# MotherBoard.net
KiCad netlist of a schematic drawn in EAGLE
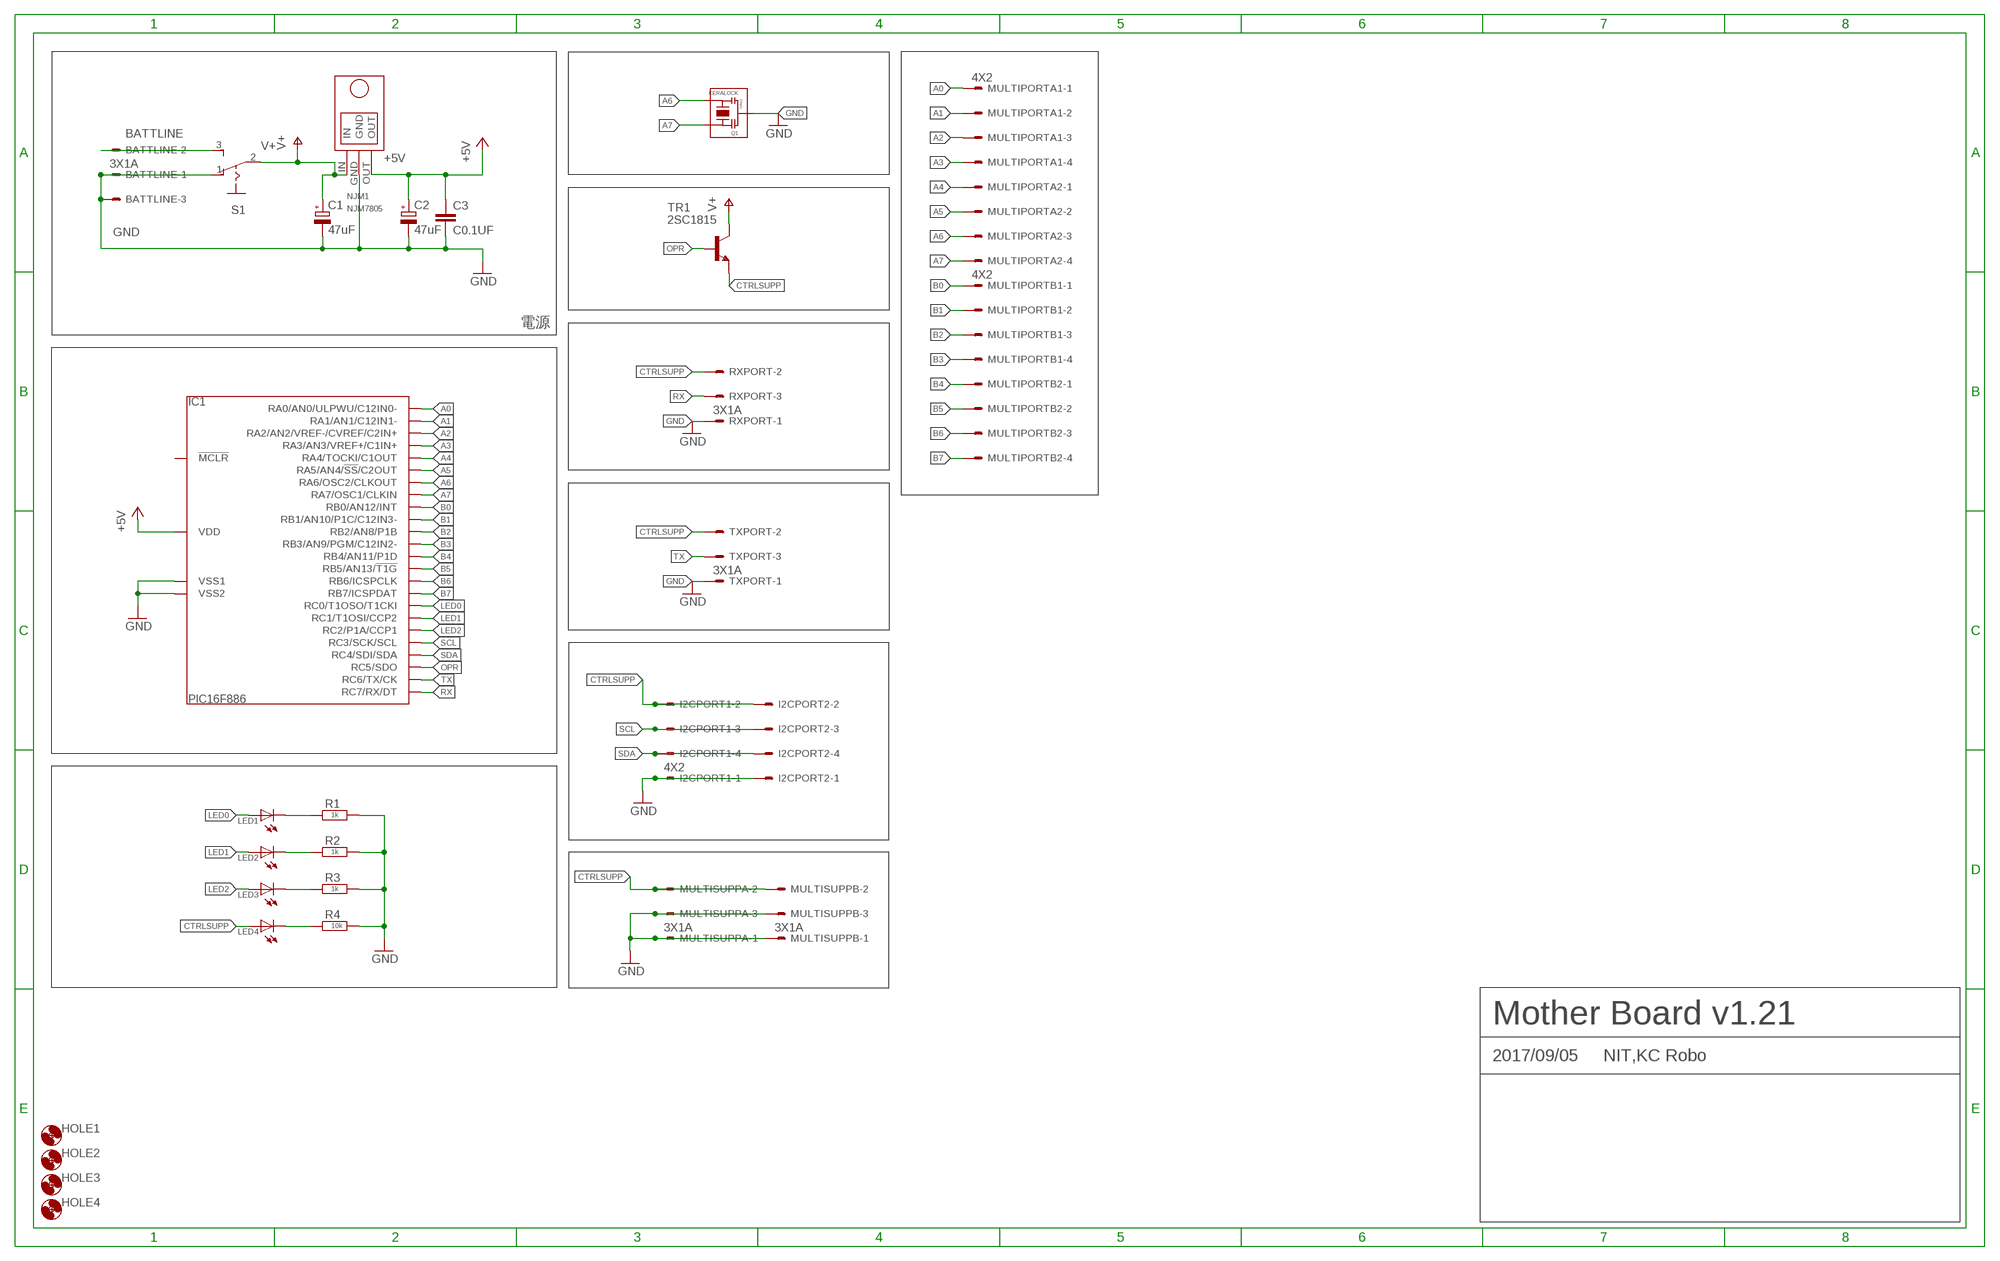
[diagram p0: schematic, sheet 1]

(export (version "E")
  (design (tool "Eeschema 10.0.6"))
  (components
    (comp (ref "BATTLINE")
      (value "3X1A")
      (footprint "eagle-import:37203-62A3-003")
      (libsource (lib "eagle-import") (part "3X1A"))
    )
    (comp (ref "C1")
      (value "47uF")
      (footprint "eagle-import:E2-5")
      (libsource (lib "eagle-import") (part "CPOL-EU2-5MM"))
    )
    (comp (ref "C2")
      (value "47uF")
      (footprint "eagle-import:E2-5")
      (libsource (lib "eagle-import") (part "CPOL-EU2-5MM"))
    )
    (comp (ref "C3")
      (value "C0.1UF")
      (footprint "eagle-import:C0.1UF")
      (libsource (lib "eagle-import") (part "C0.1UF"))
    )
    (comp (ref "HOLE1")
      (value "HOLE3.3M3BOLT")
      (footprint "eagle-import:HOLE3.3")
      (libsource (lib "eagle-import") (part "HOLE3.3M3BOLT"))
    )
    (comp (ref "HOLE2")
      (value "HOLE3.3M3BOLT")
      (footprint "eagle-import:HOLE3.3")
      (libsource (lib "eagle-import") (part "HOLE3.3M3BOLT"))
    )
    (comp (ref "HOLE3")
      (value "HOLE3.3M3BOLT")
      (footprint "eagle-import:HOLE3.3")
      (libsource (lib "eagle-import") (part "HOLE3.3M3BOLT"))
    )
    (comp (ref "HOLE4")
      (value "HOLE3.3M3BOLT")
      (footprint "eagle-import:HOLE3.3")
      (libsource (lib "eagle-import") (part "HOLE3.3M3BOLT"))
    )
    (comp (ref "I2CPORT")
      (value "4X2")
      (footprint "eagle-import:37208-62A3-004")
      (libsource (lib "eagle-import") (part "4X2"))
    )
    (comp (ref "IC1")
      (value "PIC16F886")
      (footprint "eagle-import:DIL28")
      (libsource (lib "eagle-import") (part "PIC16F886"))
    )
    (comp (ref "LED1")
      (value "LED5MM")
      (footprint "eagle-import:LED5MM")
      (libsource (lib "eagle-import") (part "LED5MM"))
    )
    (comp (ref "LED2")
      (value "LED5MM")
      (footprint "eagle-import:LED5MM")
      (libsource (lib "eagle-import") (part "LED5MM"))
    )
    (comp (ref "LED3")
      (value "LED5MM")
      (footprint "eagle-import:LED5MM")
      (libsource (lib "eagle-import") (part "LED5MM"))
    )
    (comp (ref "LED4")
      (value "LED5MM")
      (footprint "eagle-import:LED5MM")
      (libsource (lib "eagle-import") (part "LED5MM"))
    )
    (comp (ref "MULTIPORTA")
      (value "4X2")
      (footprint "eagle-import:37208-62A3-004")
      (libsource (lib "eagle-import") (part "4X2"))
    )
    (comp (ref "MULTIPORTB")
      (value "4X2")
      (footprint "eagle-import:37208-62A3-004")
      (libsource (lib "eagle-import") (part "4X2"))
    )
    (comp (ref "MULTISUPPA")
      (value "3X1A")
      (footprint "eagle-import:37203-62A3-003")
      (libsource (lib "eagle-import") (part "3X1A"))
    )
    (comp (ref "MULTISUPPB")
      (value "3X1A")
      (footprint "eagle-import:37203-62A3-003")
      (libsource (lib "eagle-import") (part "3X1A"))
    )
    (comp (ref "NJM1")
      (value "NJM7805")
      (footprint "eagle-import:NJM7805")
      (libsource (lib "eagle-import") (part "NJM7805"))
    )
    (comp (ref "Q1")
      (value "CERALOCK")
      (footprint "eagle-import:CERALOCK")
      (libsource (lib "eagle-import") (part "CERALOCK"))
    )
    (comp (ref "R1")
      (value "1k")
      (footprint "eagle-import:R3216W")
      (libsource (lib "eagle-import") (part "R-EU_R3216W"))
    )
    (comp (ref "R2")
      (value "1k")
      (footprint "eagle-import:R3216W")
      (libsource (lib "eagle-import") (part "R-EU_R3216W"))
    )
    (comp (ref "R3")
      (value "1k")
      (footprint "eagle-import:R3216W")
      (libsource (lib "eagle-import") (part "R-EU_R3216W"))
    )
    (comp (ref "R4")
      (value "10k")
      (footprint "eagle-import:R3216W")
      (libsource (lib "eagle-import") (part "R-EU_R3216W"))
    )
    (comp (ref "RXPORT")
      (value "3X1A")
      (footprint "eagle-import:37203-62A3-003")
      (libsource (lib "eagle-import") (part "3X1A"))
    )
    (comp (ref "S1")
      (value "SLIDESW")
      (footprint "eagle-import:SLIDESW")
      (libsource (lib "eagle-import") (part "SLIDESW"))
    )
    (comp (ref "TR1")
      (value "2SC1815")
      (footprint "eagle-import:TO92-")
      (libsource (lib "eagle-import") (part "2SC1815"))
    )
    (comp (ref "TXPORT")
      (value "3X1A")
      (footprint "eagle-import:37203-62A3-003")
      (libsource (lib "eagle-import") (part "3X1A"))
    )
  )
  (nets
    (net (code "1") (name "+5V") (class "Default")
      (node (ref "C2") (pin "+") (pinfunction "+_+") (pintype "passive"))
      (node (ref "C3") (pin "1") (pinfunction "1_1") (pintype "passive"))
      (node (ref "IC1") (pin "20") (pinfunction "VDD_20") (pintype "passive"))
      (node (ref "NJM1") (pin "OUT") (pinfunction "OUT_OUT") (pintype "bidirectional"))
    )
    (net (code "2") (name "/BATTLINE") (class "Default")
      (node (ref "BATTLINE") (pin "1-2") (pinfunction "S_1-2") (pintype "passive"))
      (node (ref "S1") (pin "3") (pinfunction "3_3") (pintype "passive"))
    )
    (net (code "3") (name "A0") (class "Default")
      (node (ref "IC1") (pin "2") (pinfunction "RA0/AN0/ULPWU/C12IN0-_2") (pintype "passive"))
      (node (ref "MULTIPORTA") (pin "1-1") (pinfunction "S_1-1") (pintype "passive"))
    )
    (net (code "4") (name "A1") (class "Default")
      (node (ref "IC1") (pin "3") (pinfunction "RA1/AN1/C12IN1-_3") (pintype "passive"))
      (node (ref "MULTIPORTA") (pin "1-2") (pinfunction "S_1-2") (pintype "passive"))
    )
    (net (code "5") (name "A2") (class "Default")
      (node (ref "IC1") (pin "4") (pinfunction "RA2/AN2/VREF-/CVREF/C2IN+_4") (pintype "passive"))
      (node (ref "MULTIPORTA") (pin "1-3") (pinfunction "S_1-3") (pintype "passive"))
    )
    (net (code "6") (name "A3") (class "Default")
      (node (ref "IC1") (pin "5") (pinfunction "RA3/AN3/VREF+/C1IN+_5") (pintype "passive"))
      (node (ref "MULTIPORTA") (pin "1-4") (pinfunction "S_1-4") (pintype "passive"))
    )
    (net (code "7") (name "A4") (class "Default")
      (node (ref "IC1") (pin "6") (pinfunction "RA4/TOCKI/C1OUT_6") (pintype "passive"))
      (node (ref "MULTIPORTA") (pin "2-1") (pinfunction "S_2-1") (pintype "passive"))
    )
    (net (code "8") (name "A5") (class "Default")
      (node (ref "IC1") (pin "7") (pinfunction "RA5/AN4/~{SS}/C2OUT_7") (pintype "passive"))
      (node (ref "MULTIPORTA") (pin "2-2") (pinfunction "S_2-2") (pintype "passive"))
    )
    (net (code "9") (name "A6") (class "Default")
      (node (ref "IC1") (pin "10") (pinfunction "RA6/OSC2/CLKOUT_10") (pintype "passive"))
      (node (ref "MULTIPORTA") (pin "2-3") (pinfunction "S_2-3") (pintype "passive"))
      (node (ref "Q1") (pin "P$3") (pinfunction "P$3_P$3") (pintype "passive"))
    )
    (net (code "10") (name "A7") (class "Default")
      (node (ref "IC1") (pin "9") (pinfunction "RA7/OSC1/CLKIN_9") (pintype "passive"))
      (node (ref "MULTIPORTA") (pin "2-4") (pinfunction "S_2-4") (pintype "passive"))
      (node (ref "Q1") (pin "P$1") (pinfunction "P$1_P$1") (pintype "passive"))
    )
    (net (code "11") (name "B0") (class "Default")
      (node (ref "IC1") (pin "21") (pinfunction "RB0/AN12/INT_21") (pintype "passive"))
      (node (ref "MULTIPORTB") (pin "1-1") (pinfunction "S_1-1") (pintype "passive"))
    )
    (net (code "12") (name "B1") (class "Default")
      (node (ref "IC1") (pin "22") (pinfunction "RB1/AN10/P1C/C12IN3-_22") (pintype "passive"))
      (node (ref "MULTIPORTB") (pin "1-2") (pinfunction "S_1-2") (pintype "passive"))
    )
    (net (code "13") (name "B2") (class "Default")
      (node (ref "IC1") (pin "23") (pinfunction "RB2/AN8/P1B_23") (pintype "passive"))
      (node (ref "MULTIPORTB") (pin "1-3") (pinfunction "S_1-3") (pintype "passive"))
    )
    (net (code "14") (name "B3") (class "Default")
      (node (ref "IC1") (pin "24") (pinfunction "RB3/AN9/PGM/C12IN2-_24") (pintype "passive"))
      (node (ref "MULTIPORTB") (pin "1-4") (pinfunction "S_1-4") (pintype "passive"))
    )
    (net (code "15") (name "B4") (class "Default")
      (node (ref "IC1") (pin "25") (pinfunction "RB4/AN11/P1D_25") (pintype "passive"))
      (node (ref "MULTIPORTB") (pin "2-1") (pinfunction "S_2-1") (pintype "passive"))
    )
    (net (code "16") (name "B5") (class "Default")
      (node (ref "IC1") (pin "26") (pinfunction "RB5/AN13/~{T1G}_26") (pintype "passive"))
      (node (ref "MULTIPORTB") (pin "2-2") (pinfunction "S_2-2") (pintype "passive"))
    )
    (net (code "17") (name "B6") (class "Default")
      (node (ref "IC1") (pin "27") (pinfunction "RB6/ICSPCLK_27") (pintype "passive"))
      (node (ref "MULTIPORTB") (pin "2-3") (pinfunction "S_2-3") (pintype "passive"))
    )
    (net (code "18") (name "B7") (class "Default")
      (node (ref "IC1") (pin "28") (pinfunction "RB7/ICSPDAT_28") (pintype "passive"))
      (node (ref "MULTIPORTB") (pin "2-4") (pinfunction "S_2-4") (pintype "passive"))
    )
    (net (code "19") (name "CTRLSUPP") (class "Default")
      (node (ref "I2CPORT") (pin "1-2") (pinfunction "S_1-2") (pintype "passive"))
      (node (ref "I2CPORT") (pin "2-2") (pinfunction "S_2-2") (pintype "passive"))
      (node (ref "LED4") (pin "A") (pinfunction "A_A") (pintype "passive"))
      (node (ref "MULTISUPPA") (pin "1-2") (pinfunction "S_1-2") (pintype "passive"))
      (node (ref "MULTISUPPB") (pin "1-2") (pinfunction "S_1-2") (pintype "passive"))
      (node (ref "RXPORT") (pin "1-2") (pinfunction "S_1-2") (pintype "passive"))
      (node (ref "TR1") (pin "E") (pinfunction "E_E") (pintype "passive"))
      (node (ref "TXPORT") (pin "1-2") (pinfunction "S_1-2") (pintype "passive"))
    )
    (net (code "20") (name "GND") (class "Default")
      (node (ref "BATTLINE") (pin "1-1") (pinfunction "S_1-1") (pintype "passive"))
      (node (ref "BATTLINE") (pin "1-3") (pinfunction "S_1-3") (pintype "passive"))
      (node (ref "C1") (pin "-") (pinfunction "-_-") (pintype "passive"))
      (node (ref "C2") (pin "-") (pinfunction "-_-") (pintype "passive"))
      (node (ref "C3") (pin "2") (pinfunction "2_2") (pintype "passive"))
      (node (ref "I2CPORT") (pin "1-1") (pinfunction "S_1-1") (pintype "passive"))
      (node (ref "I2CPORT") (pin "2-1") (pinfunction "S_2-1") (pintype "passive"))
      (node (ref "IC1") (pin "19") (pinfunction "VSS2_19") (pintype "passive"))
      (node (ref "IC1") (pin "8") (pinfunction "VSS1_8") (pintype "passive"))
      (node (ref "MULTISUPPA") (pin "1-1") (pinfunction "S_1-1") (pintype "passive"))
      (node (ref "MULTISUPPA") (pin "1-3") (pinfunction "S_1-3") (pintype "passive"))
      (node (ref "MULTISUPPB") (pin "1-1") (pinfunction "S_1-1") (pintype "passive"))
      (node (ref "MULTISUPPB") (pin "1-3") (pinfunction "S_1-3") (pintype "passive"))
      (node (ref "NJM1") (pin "GND") (pinfunction "GND_GND") (pintype "bidirectional"))
      (node (ref "Q1") (pin "P$2") (pinfunction "P$2_P$2") (pintype "passive"))
      (node (ref "R1") (pin "2") (pinfunction "2_2") (pintype "passive"))
      (node (ref "R2") (pin "2") (pinfunction "2_2") (pintype "passive"))
      (node (ref "R3") (pin "2") (pinfunction "2_2") (pintype "passive"))
      (node (ref "R4") (pin "2") (pinfunction "2_2") (pintype "passive"))
      (node (ref "RXPORT") (pin "1-1") (pinfunction "S_1-1") (pintype "passive"))
      (node (ref "S1") (pin "1") (pinfunction "1_1") (pintype "passive"))
      (node (ref "TXPORT") (pin "1-1") (pinfunction "S_1-1") (pintype "passive"))
    )
    (net (code "21") (name "LED0") (class "Default")
      (node (ref "IC1") (pin "11") (pinfunction "RC0/T1OSO/T1CKI_11") (pintype "passive"))
      (node (ref "LED1") (pin "A") (pinfunction "A_A") (pintype "passive"))
    )
    (net (code "22") (name "LED1") (class "Default")
      (node (ref "IC1") (pin "12") (pinfunction "RC1/T1OSI/CCP2_12") (pintype "passive"))
      (node (ref "LED2") (pin "A") (pinfunction "A_A") (pintype "passive"))
    )
    (net (code "23") (name "LED2") (class "Default")
      (node (ref "IC1") (pin "13") (pinfunction "RC2/P1A/CCP1_13") (pintype "passive"))
      (node (ref "LED3") (pin "A") (pinfunction "A_A") (pintype "passive"))
    )
    (net (code "24") (name "Net-(LED1-C)") (class "Default")
      (node (ref "LED1") (pin "K") (pinfunction "C_K") (pintype "passive"))
      (node (ref "R1") (pin "1") (pinfunction "1_1") (pintype "passive"))
    )
    (net (code "25") (name "Net-(LED2-C)") (class "Default")
      (node (ref "LED2") (pin "K") (pinfunction "C_K") (pintype "passive"))
      (node (ref "R2") (pin "1") (pinfunction "1_1") (pintype "passive"))
    )
    (net (code "26") (name "Net-(LED3-C)") (class "Default")
      (node (ref "LED3") (pin "K") (pinfunction "C_K") (pintype "passive"))
      (node (ref "R3") (pin "1") (pinfunction "1_1") (pintype "passive"))
    )
    (net (code "27") (name "Net-(LED4-C)") (class "Default")
      (node (ref "LED4") (pin "K") (pinfunction "C_K") (pintype "passive"))
      (node (ref "R4") (pin "1") (pinfunction "1_1") (pintype "passive"))
    )
    (net (code "28") (name "OPR") (class "Default")
      (node (ref "IC1") (pin "16") (pinfunction "RC5/SDO_16") (pintype "passive"))
      (node (ref "TR1") (pin "B") (pinfunction "B_B") (pintype "passive"))
    )
    (net (code "29") (name "RX") (class "Default")
      (node (ref "IC1") (pin "18") (pinfunction "RC7/RX/DT_18") (pintype "passive"))
      (node (ref "RXPORT") (pin "1-3") (pinfunction "S_1-3") (pintype "passive"))
    )
    (net (code "30") (name "SCL") (class "Default")
      (node (ref "I2CPORT") (pin "1-3") (pinfunction "S_1-3") (pintype "passive"))
      (node (ref "I2CPORT") (pin "2-3") (pinfunction "S_2-3") (pintype "passive"))
      (node (ref "IC1") (pin "14") (pinfunction "RC3/SCK/SCL_14") (pintype "passive"))
    )
    (net (code "31") (name "SDA") (class "Default")
      (node (ref "I2CPORT") (pin "1-4") (pinfunction "S_1-4") (pintype "passive"))
      (node (ref "I2CPORT") (pin "2-4") (pinfunction "S_2-4") (pintype "passive"))
      (node (ref "IC1") (pin "15") (pinfunction "RC4/SDI/SDA_15") (pintype "passive"))
    )
    (net (code "32") (name "TX") (class "Default")
      (node (ref "IC1") (pin "17") (pinfunction "RC6/TX/CK_17") (pintype "passive"))
      (node (ref "TXPORT") (pin "1-3") (pinfunction "S_1-3") (pintype "passive"))
    )
    (net (code "33") (name "V+") (class "Default")
      (node (ref "C1") (pin "+") (pinfunction "+_+") (pintype "passive"))
      (node (ref "NJM1") (pin "IN") (pinfunction "IN_IN") (pintype "bidirectional"))
      (node (ref "S1") (pin "2") (pinfunction "2_2") (pintype "passive"))
      (node (ref "TR1") (pin "C") (pinfunction "C_C") (pintype "passive"))
    )
    (net (code "34") (name "unconnected-(IC1-~{MCLR}-Pad1)") (class "Default")
      (node (ref "IC1") (pin "1") (pinfunction "~{MCLR}_1") (pintype "passive"))
    )
  )
)
